# Perifericos.net
KiCad netlist of a schematic drawn in Altium Designer
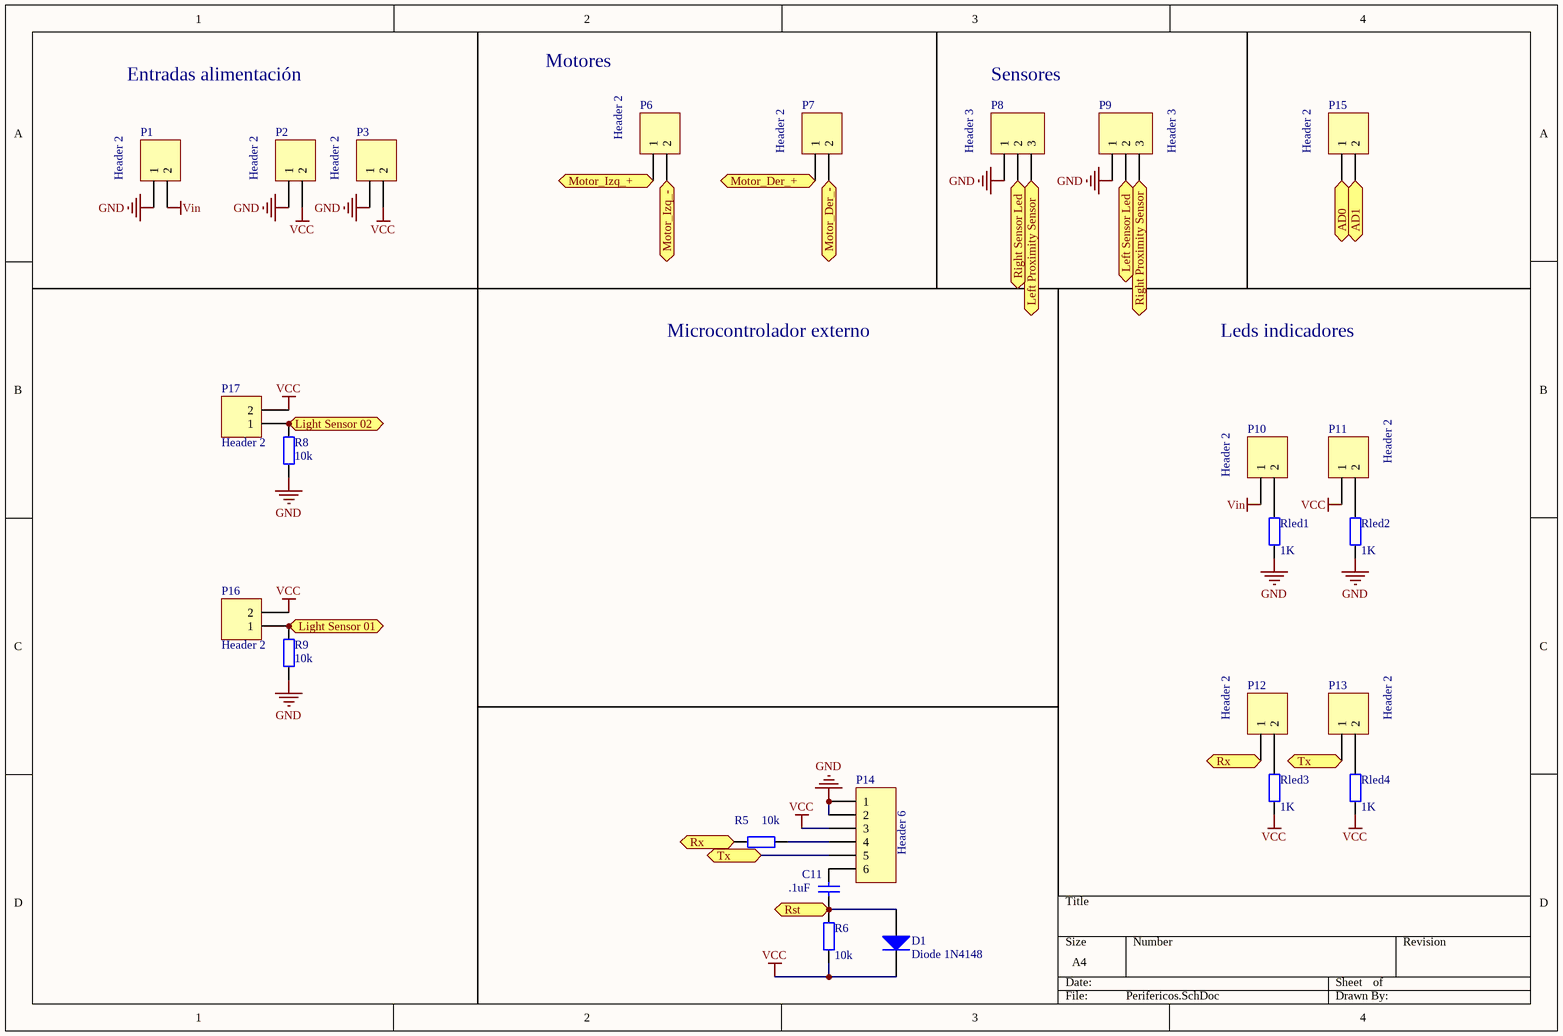
[diagram p0: Perifericos.SchDoc]

(export (version "E")
  (design (tool "Eeschema 10.0.6"))
  (components
    (comp (ref "C11")
      (value ".1uF")
      (footprint "RAD-0.3")
      (description "Capacitor")
      (fields (field (name "Comment") "Cap") (field (name "PUBLISHER") "Altium Limited"))
      (libsource (lib "Miscellaneous Devices") (part "Cap"))
    )
    (comp (ref "D1")
      (value "Diode 1N4148")
      (footprint "DO-35")
      (description "High Conductance Fast Diode")
      (fields (field (name "PUBLISHER") "Altium Limited"))
      (libsource (lib "Miscellaneous Devices") (part "Diode 1N4148"))
    )
    (comp (ref "P1")
      (value "Header 2")
      (footprint "HDR1X2")
      (description "Header, 2-Pin")
      (fields (field (name "PUBLISHER") "Altium Limited"))
      (libsource (lib "Miscellaneous Connectors") (part "Header 2"))
    )
    (comp (ref "P2")
      (value "Header 2")
      (footprint "HDR1X2")
      (description "Header, 2-Pin")
      (fields (field (name "PUBLISHER") "Altium Limited"))
      (libsource (lib "Miscellaneous Connectors") (part "Header 2"))
    )
    (comp (ref "P3")
      (value "Header 2")
      (footprint "HDR1X2")
      (description "Header, 2-Pin")
      (fields (field (name "PUBLISHER") "Altium Limited"))
      (libsource (lib "Miscellaneous Connectors") (part "Header 2"))
    )
    (comp (ref "P6")
      (value "Header 2")
      (footprint "HDR1X2")
      (description "Header, 2-Pin")
      (fields (field (name "PUBLISHER") "Altium Limited"))
      (libsource (lib "Miscellaneous Connectors") (part "Header 2"))
    )
    (comp (ref "P7")
      (value "Header 2")
      (footprint "HDR1X2")
      (description "Header, 2-Pin")
      (fields (field (name "PUBLISHER") "Altium Limited"))
      (libsource (lib "Miscellaneous Connectors") (part "Header 2"))
    )
    (comp (ref "P8")
      (value "Header 3")
      (footprint "HDR1X3")
      (description "Header, 3-Pin")
      (fields (field (name "PUBLISHER") "Altium Limited"))
      (libsource (lib "Miscellaneous Connectors") (part "Header 3"))
    )
    (comp (ref "P9")
      (value "Header 3")
      (footprint "HDR1X3")
      (description "Header, 3-Pin")
      (fields (field (name "PUBLISHER") "Altium Limited"))
      (libsource (lib "Miscellaneous Connectors") (part "Header 3"))
    )
    (comp (ref "P10")
      (value "Header 2")
      (footprint "HDR1X2")
      (description "Header, 2-Pin")
      (fields (field (name "PUBLISHER") "Altium Limited"))
      (libsource (lib "Miscellaneous Connectors") (part "Header 2"))
    )
    (comp (ref "P11")
      (value "Header 2")
      (footprint "HDR1X2")
      (description "Header, 2-Pin")
      (fields (field (name "PUBLISHER") "Altium Limited"))
      (libsource (lib "Miscellaneous Connectors") (part "Header 2"))
    )
    (comp (ref "P12")
      (value "Header 2")
      (footprint "HDR1X2")
      (description "Header, 2-Pin")
      (fields (field (name "PUBLISHER") "Altium Limited"))
      (libsource (lib "Miscellaneous Connectors") (part "Header 2"))
    )
    (comp (ref "P13")
      (value "Header 2")
      (footprint "HDR1X2")
      (description "Header, 2-Pin")
      (fields (field (name "PUBLISHER") "Altium Limited"))
      (libsource (lib "Miscellaneous Connectors") (part "Header 2"))
    )
    (comp (ref "P14")
      (value "Header 6")
      (footprint "HDR1X6")
      (description "Header, 6-Pin")
      (fields (field (name "PUBLISHER") "Altium Limited"))
      (libsource (lib "Miscellaneous Connectors") (part "Header 6"))
    )
    (comp (ref "P15")
      (value "Header 2")
      (footprint "HDR1X2")
      (description "Header, 2-Pin")
      (fields (field (name "PUBLISHER") "Altium Limited"))
      (libsource (lib "Miscellaneous Connectors") (part "Header 2"))
    )
    (comp (ref "P16")
      (value "Header 2")
      (footprint "HDR1X2")
      (description "Header, 2-Pin")
      (fields (field (name "PUBLISHER") "Altium Limited"))
      (libsource (lib "") (part "Header 2_1"))
    )
    (comp (ref "P17")
      (value "Header 2")
      (footprint "HDR1X2")
      (description "Header, 2-Pin")
      (fields (field (name "PUBLISHER") "Altium Limited"))
      (libsource (lib "") (part "Header 2_1"))
    )
    (comp (ref "R5")
      (value "10k")
      (footprint "AXIAL-0.4")
      (description "Resistor")
      (fields (field (name "Comment") "Res2") (field (name "PUBLISHER") "Altium Limited"))
      (libsource (lib "") (part "Res2_1"))
    )
    (comp (ref "R6")
      (value "10k")
      (footprint "AXIAL-0.4")
      (description "Resistor")
      (fields (field (name "Comment") "Res2") (field (name "PUBLISHER") "Altium Limited"))
      (libsource (lib "Miscellaneous Devices") (part "Res2"))
    )
    (comp (ref "R8")
      (value "10k")
      (footprint "AXIAL-0.4")
      (description "Resistor")
      (fields (field (name "Comment") "Res2") (field (name "PUBLISHER") "Altium Limited"))
      (libsource (lib "Miscellaneous Devices") (part "Res2"))
    )
    (comp (ref "R9")
      (value "10k")
      (footprint "AXIAL-0.4")
      (description "Resistor")
      (fields (field (name "Comment") "Res2") (field (name "PUBLISHER") "Altium Limited"))
      (libsource (lib "Miscellaneous Devices") (part "Res2"))
    )
    (comp (ref "Rled1")
      (value "1K")
      (footprint "AXIAL-0.4")
      (description "Resistor")
      (fields (field (name "Comment") "Res2") (field (name "PUBLISHER") "Altium Limited"))
      (libsource (lib "Miscellaneous Devices") (part "Res2"))
    )
    (comp (ref "Rled2")
      (value "1K")
      (footprint "AXIAL-0.4")
      (description "Resistor")
      (fields (field (name "Comment") "Res2") (field (name "PUBLISHER") "Altium Limited"))
      (libsource (lib "Miscellaneous Devices") (part "Res2"))
    )
    (comp (ref "Rled3")
      (value "1K")
      (footprint "AXIAL-0.4")
      (description "Resistor")
      (fields (field (name "Comment") "Res2") (field (name "PUBLISHER") "Altium Limited"))
      (libsource (lib "Miscellaneous Devices") (part "Res2"))
    )
    (comp (ref "Rled4")
      (value "1K")
      (footprint "AXIAL-0.4")
      (description "Resistor")
      (fields (field (name "Comment") "Res2") (field (name "PUBLISHER") "Altium Limited"))
      (libsource (lib "Miscellaneous Devices") (part "Res2"))
    )
  )
  (nets
    (net (code "1") (name "/AD0") (class "Default")
      (node (ref "P15") (pin "1") (pinfunction "1_1") (pintype "passive"))
    )
    (net (code "2") (name "/AD1") (class "Default")
      (node (ref "P15") (pin "2") (pinfunction "2_2") (pintype "passive"))
    )
    (net (code "3") (name "/Left Proximity Sensor") (class "Default")
      (node (ref "P8") (pin "3") (pinfunction "3_3") (pintype "passive"))
    )
    (net (code "4") (name "/Left Sensor Led") (class "Default")
      (node (ref "P9") (pin "2") (pinfunction "2_2") (pintype "passive"))
    )
    (net (code "5") (name "/Light Sensor 01") (class "Default")
      (node (ref "P16") (pin "1") (pinfunction "1_1") (pintype "passive"))
      (node (ref "R9") (pin "2") (pinfunction "2_2") (pintype "passive"))
    )
    (net (code "6") (name "/Light Sensor 02") (class "Default")
      (node (ref "P17") (pin "1") (pinfunction "1_1") (pintype "passive"))
      (node (ref "R8") (pin "2") (pinfunction "2_2") (pintype "passive"))
    )
    (net (code "7") (name "/Motor_Der_+") (class "Default")
      (node (ref "P7") (pin "1") (pinfunction "1_1") (pintype "passive"))
    )
    (net (code "8") (name "/Motor_Der_-") (class "Default")
      (node (ref "P7") (pin "2") (pinfunction "2_2") (pintype "passive"))
    )
    (net (code "9") (name "/Motor_Izq_+") (class "Default")
      (node (ref "P6") (pin "1") (pinfunction "1_1") (pintype "passive"))
    )
    (net (code "10") (name "/Motor_Izq_-") (class "Default")
      (node (ref "P6") (pin "2") (pinfunction "2_2") (pintype "passive"))
    )
    (net (code "11") (name "/Right Proximity Sensor") (class "Default")
      (node (ref "P9") (pin "3") (pinfunction "3_3") (pintype "passive"))
    )
    (net (code "12") (name "/Right Sensor Led") (class "Default")
      (node (ref "P8") (pin "2") (pinfunction "2_2") (pintype "passive"))
    )
    (net (code "13") (name "/Rst") (class "Default")
      (node (ref "C11") (pin "1") (pinfunction "1_1") (pintype "passive"))
      (node (ref "D1") (pin "1") (pinfunction "A_1") (pintype "passive"))
      (node (ref "R6") (pin "2") (pinfunction "2_2") (pintype "passive"))
    )
    (net (code "14") (name "/Rx") (class "Default")
      (node (ref "P12") (pin "1") (pinfunction "1_1") (pintype "passive"))
      (node (ref "R5") (pin "1") (pinfunction "1_1") (pintype "passive"))
    )
    (net (code "15") (name "/Tx") (class "Default")
      (node (ref "P13") (pin "1") (pinfunction "1_1") (pintype "passive"))
      (node (ref "P14") (pin "5") (pinfunction "5_5") (pintype "passive"))
    )
    (net (code "16") (name "GND") (class "Default")
      (node (ref "P1") (pin "1") (pinfunction "1_1") (pintype "passive"))
      (node (ref "P14") (pin "1") (pinfunction "1_1") (pintype "passive"))
      (node (ref "P14") (pin "2") (pinfunction "2_2") (pintype "passive"))
      (node (ref "P2") (pin "1") (pinfunction "1_1") (pintype "passive"))
      (node (ref "P3") (pin "1") (pinfunction "1_1") (pintype "passive"))
      (node (ref "P8") (pin "1") (pinfunction "1_1") (pintype "passive"))
      (node (ref "P9") (pin "1") (pinfunction "1_1") (pintype "passive"))
      (node (ref "R8") (pin "1") (pinfunction "1_1") (pintype "passive"))
      (node (ref "R9") (pin "1") (pinfunction "1_1") (pintype "passive"))
      (node (ref "Rled1") (pin "1") (pinfunction "1_1") (pintype "passive"))
      (node (ref "Rled2") (pin "1") (pinfunction "1_1") (pintype "passive"))
    )
    (net (code "17") (name "Net-(C11-Pad2)") (class "Default")
      (node (ref "C11") (pin "2") (pinfunction "2_2") (pintype "passive"))
      (node (ref "P14") (pin "6") (pinfunction "6_6") (pintype "passive"))
    )
    (net (code "18") (name "Net-(P10-Pad2)") (class "Default")
      (node (ref "P10") (pin "2") (pinfunction "2_2") (pintype "passive"))
      (node (ref "Rled1") (pin "2") (pinfunction "2_2") (pintype "passive"))
    )
    (net (code "19") (name "Net-(P11-Pad2)") (class "Default")
      (node (ref "P11") (pin "2") (pinfunction "2_2") (pintype "passive"))
      (node (ref "Rled2") (pin "2") (pinfunction "2_2") (pintype "passive"))
    )
    (net (code "20") (name "Net-(P12-Pad2)") (class "Default")
      (node (ref "P12") (pin "2") (pinfunction "2_2") (pintype "passive"))
      (node (ref "Rled3") (pin "2") (pinfunction "2_2") (pintype "passive"))
    )
    (net (code "21") (name "Net-(P13-Pad2)") (class "Default")
      (node (ref "P13") (pin "2") (pinfunction "2_2") (pintype "passive"))
      (node (ref "Rled4") (pin "2") (pinfunction "2_2") (pintype "passive"))
    )
    (net (code "22") (name "Net-(P14-Pad4)") (class "Default")
      (node (ref "P14") (pin "4") (pinfunction "4_4") (pintype "passive"))
      (node (ref "R5") (pin "2") (pinfunction "2_2") (pintype "passive"))
    )
    (net (code "23") (name "VCC") (class "Default")
      (node (ref "D1") (pin "2") (pinfunction "K_2") (pintype "passive"))
      (node (ref "P11") (pin "1") (pinfunction "1_1") (pintype "passive"))
      (node (ref "P14") (pin "3") (pinfunction "3_3") (pintype "passive"))
      (node (ref "P16") (pin "2") (pinfunction "2_2") (pintype "passive"))
      (node (ref "P17") (pin "2") (pinfunction "2_2") (pintype "passive"))
      (node (ref "P2") (pin "2") (pinfunction "2_2") (pintype "passive"))
      (node (ref "P3") (pin "2") (pinfunction "2_2") (pintype "passive"))
      (node (ref "R6") (pin "1") (pinfunction "1_1") (pintype "passive"))
      (node (ref "Rled3") (pin "1") (pinfunction "1_1") (pintype "passive"))
      (node (ref "Rled4") (pin "1") (pinfunction "1_1") (pintype "passive"))
    )
    (net (code "24") (name "Vin") (class "Default")
      (node (ref "P1") (pin "2") (pinfunction "2_2") (pintype "passive"))
      (node (ref "P10") (pin "1") (pinfunction "1_1") (pintype "passive"))
    )
  )
)
